# F407ULPI_externalDAC.net
KiCad netlist of a schematic drawn in Altium Designer
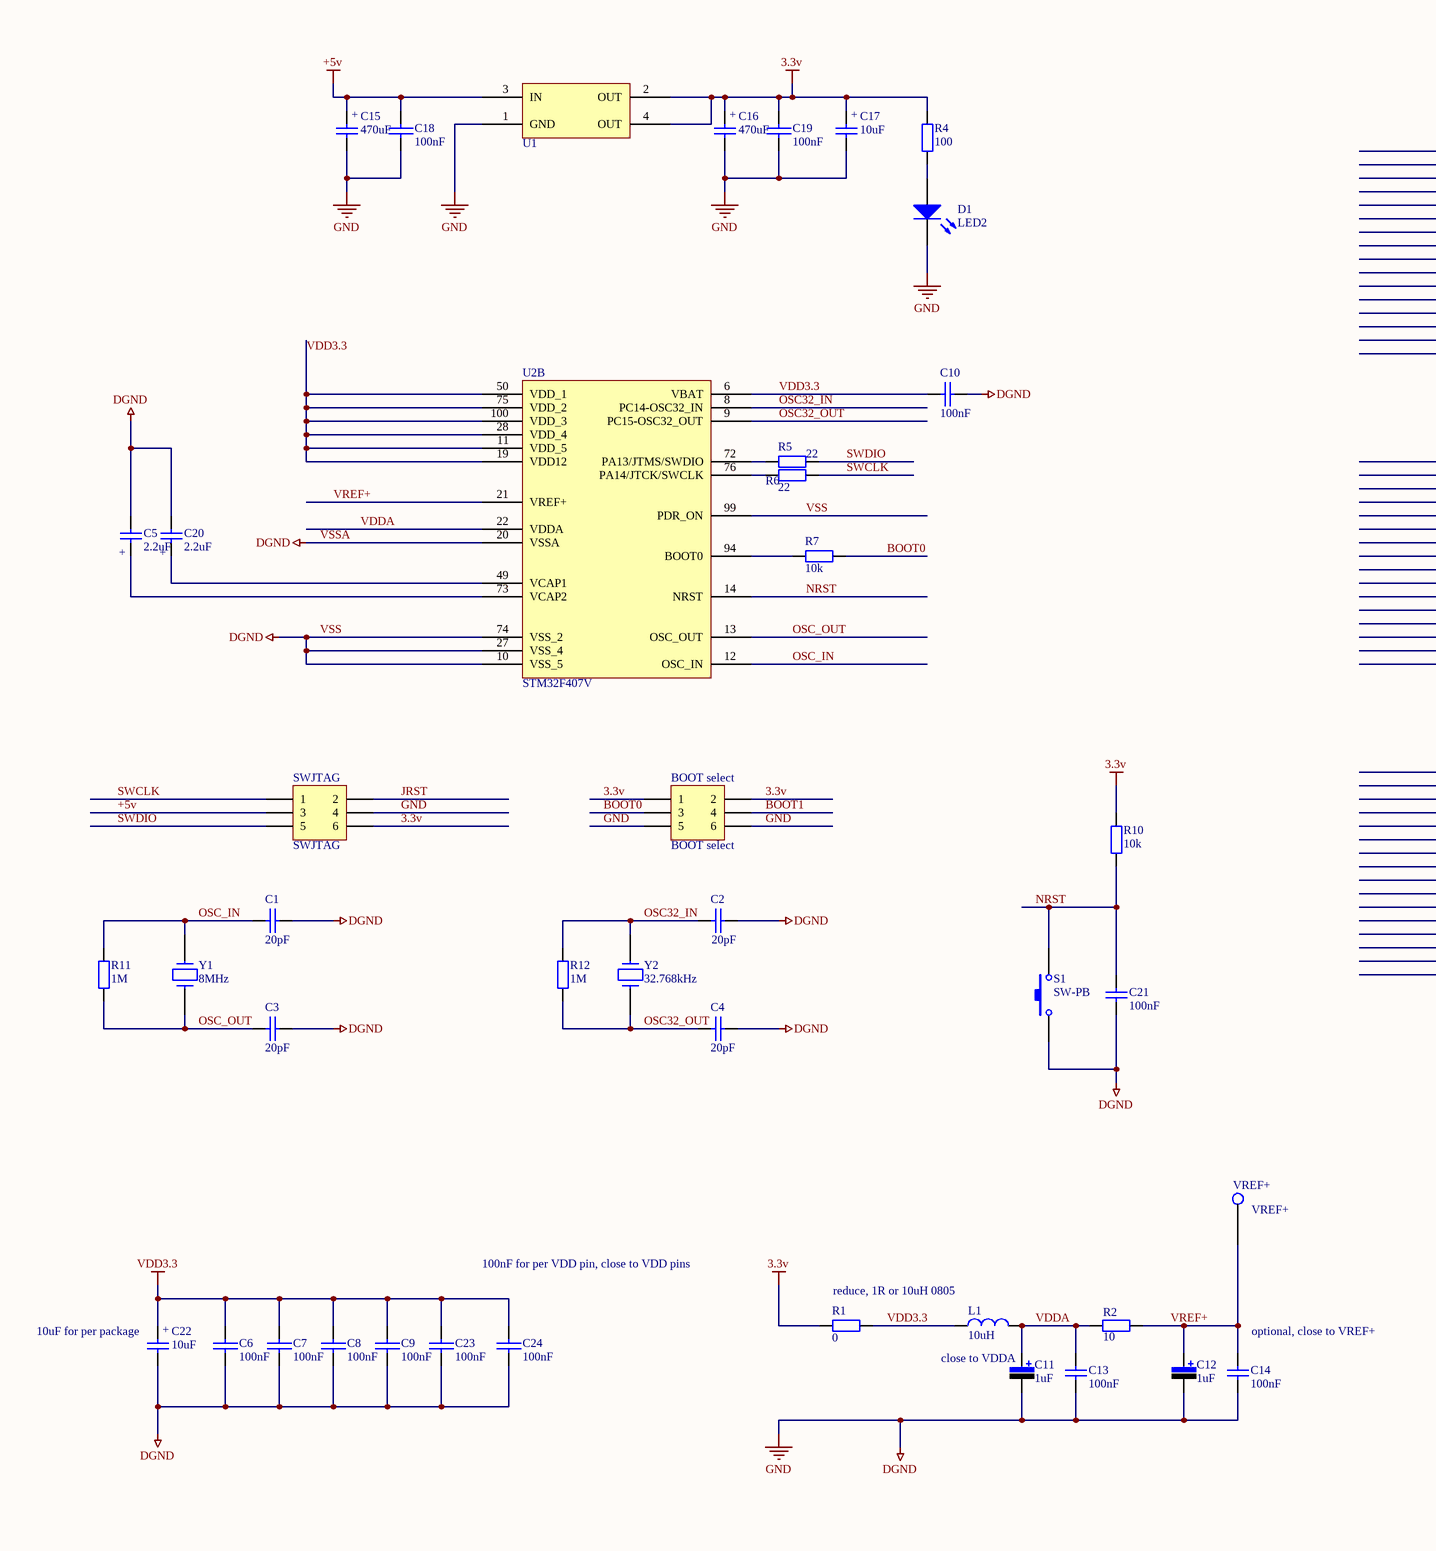
[diagram p0: F407ULPI&externalDAC.SchDoc, left]
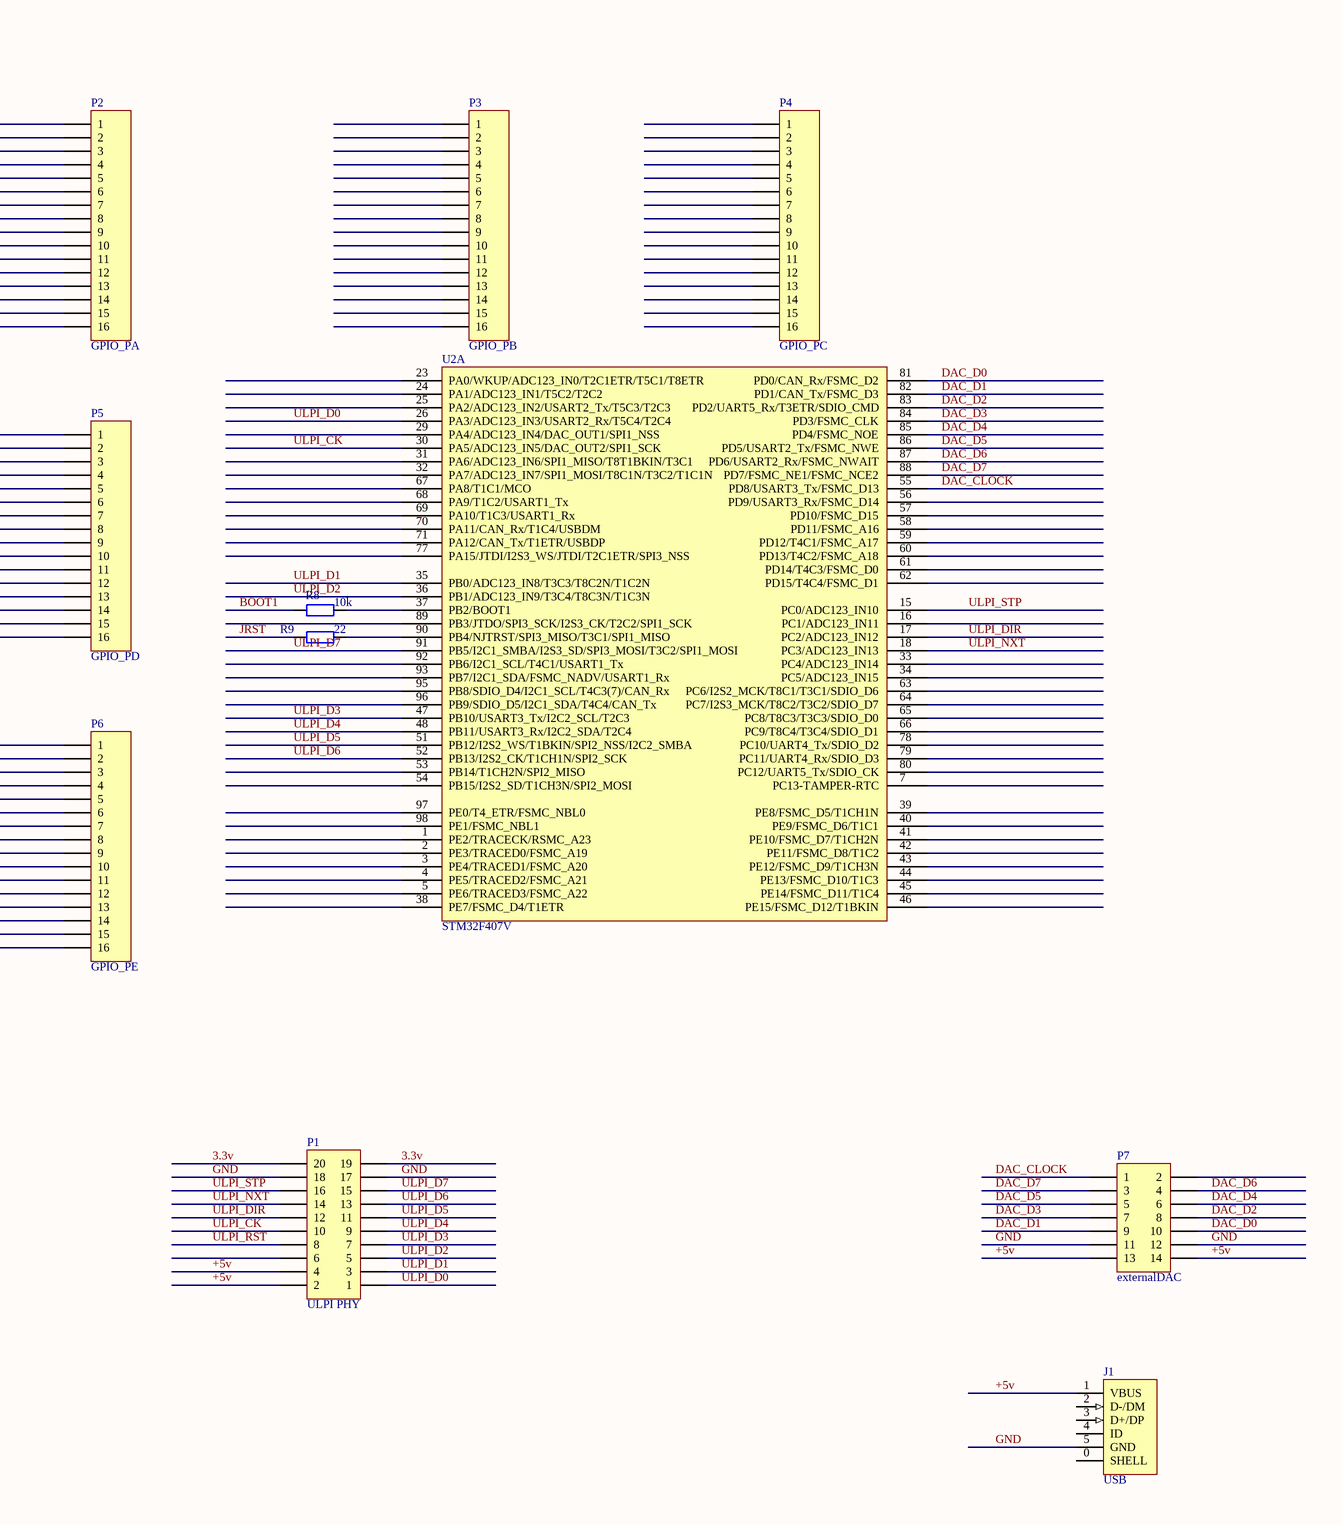
[diagram p1: F407ULPI&externalDAC.SchDoc, right]

(export (version "E")
  (design (tool "Eeschema 10.0.6"))
  (components
    (comp (ref "BOOT select")
      (value "BOOT select")
      (footprint "HDR2X3_CEN")
      (description "Header, 3-Pin, Dual row")
      (fields (field (name "PUBLISHER") "Altium Limited"))
      (libsource (lib "SkyWorks2") (part "Header 3X2"))
    )
    (comp (ref "C1")
      (value "20pF")
      (footprint "CAP-0603")
      (description "贴片无极性电容")
      (fields (field (name "Comment") "cap smd"))
      (libsource (lib "SkyWorks2") (part "CAP"))
    )
    (comp (ref "C2")
      (value "20pF")
      (footprint "CAP-0603")
      (description "贴片无极性电容")
      (fields (field (name "Comment") "cap smd"))
      (libsource (lib "SkyWorks2") (part "CAP"))
    )
    (comp (ref "C3")
      (value "20pF")
      (footprint "CAP-0603")
      (description "贴片无极性电容")
      (fields (field (name "Comment") "cap smd"))
      (libsource (lib "SkyWorks2") (part "CAP"))
    )
    (comp (ref "C4")
      (value "20pF")
      (footprint "CAP-0603")
      (description "贴片无极性电容")
      (fields (field (name "Comment") "cap smd"))
      (libsource (lib "SkyWorks2") (part "CAP"))
    )
    (comp (ref "C5")
      (value "2.2uF")
      (footprint "CAP-3216")
      (description "贴片极性电容")
      (fields (field (name "Comment") "Cap"))
      (libsource (lib "SkyWorks2") (part "Cap Pol S"))
    )
    (comp (ref "C6")
      (value "100nF")
      (footprint "CAP-0603")
      (description "贴片无极性电容")
      (fields (field (name "Comment") "cap smd"))
      (libsource (lib "SkyWorks2") (part "CAP"))
    )
    (comp (ref "C7")
      (value "100nF")
      (footprint "CAP-0603")
      (description "贴片无极性电容")
      (fields (field (name "Comment") "cap smd"))
      (libsource (lib "SkyWorks2") (part "CAP"))
    )
    (comp (ref "C8")
      (value "100nF")
      (footprint "CAP-0603")
      (description "贴片无极性电容")
      (fields (field (name "Comment") "cap smd"))
      (libsource (lib "SkyWorks2") (part "CAP"))
    )
    (comp (ref "C9")
      (value "100nF")
      (footprint "CAP-0603")
      (description "贴片无极性电容")
      (fields (field (name "Comment") "cap smd"))
      (libsource (lib "SkyWorks2") (part "CAP"))
    )
    (comp (ref "C10")
      (value "100nF")
      (footprint "CAP-0603")
      (description "贴片无极性电容")
      (fields (field (name "Comment") "cap smd"))
      (libsource (lib "SkyWorks2") (part "CAP"))
    )
    (comp (ref "C11")
      (value "1uF")
      (footprint "CAP-3216")
      (description "极性电解电容")
      (fields (field (name "Comment") "Cap Pol") (field (name "PUBLISHER") "Altium Limited"))
      (libsource (lib "Fszhang") (part "Cap Pol"))
    )
    (comp (ref "C12")
      (value "1uF")
      (footprint "CAP-3216")
      (description "极性电解电容")
      (fields (field (name "Comment") "Cap Pol") (field (name "PUBLISHER") "Altium Limited"))
      (libsource (lib "Fszhang") (part "Cap Pol"))
    )
    (comp (ref "C13")
      (value "100nF")
      (footprint "CAP-0603")
      (description "无极性电容")
      (fields (field (name "Comment") "Cap") (field (name "PUBLISHER") "Altium Limited"))
      (libsource (lib "Fszhang") (part "Cap"))
    )
    (comp (ref "C14")
      (value "100nF")
      (footprint "CAP-0603")
      (description "无极性电容")
      (fields (field (name "Comment") "Cap") (field (name "PUBLISHER") "Altium Limited"))
      (libsource (lib "Fszhang") (part "Cap"))
    )
    (comp (ref "C15")
      (value "470uF")
      (footprint "CAP-7343")
      (description "贴片极性电容")
      (fields (field (name "Comment") "Cap"))
      (libsource (lib "SkyWorks2") (part "Cap Pol S"))
    )
    (comp (ref "C16")
      (value "470uF")
      (footprint "CAP-7343")
      (description "贴片极性电容")
      (fields (field (name "Comment") "Cap"))
      (libsource (lib "SkyWorks2") (part "Cap Pol S"))
    )
    (comp (ref "C17")
      (value "10uF")
      (footprint "CAP-3216")
      (description "贴片极性电容")
      (fields (field (name "Comment") "Cap"))
      (libsource (lib "SkyWorks2") (part "Cap Pol S"))
    )
    (comp (ref "C18")
      (value "100nF")
      (footprint "CAP-0603")
      (description "贴片无极性电容")
      (fields (field (name "Comment") "cap smd"))
      (libsource (lib "SkyWorks2") (part "CAP"))
    )
    (comp (ref "C19")
      (value "100nF")
      (footprint "CAP-0603")
      (description "贴片无极性电容")
      (fields (field (name "Comment") "cap smd"))
      (libsource (lib "SkyWorks2") (part "CAP"))
    )
    (comp (ref "C20")
      (value "2.2uF")
      (footprint "CAP-3216")
      (description "贴片极性电容")
      (fields (field (name "Comment") "Cap"))
      (libsource (lib "SkyWorks2") (part "Cap Pol S"))
    )
    (comp (ref "C21")
      (value "100nF")
      (footprint "CAP-0603")
      (description "无极性电容")
      (fields (field (name "Comment") "Cap") (field (name "PUBLISHER") "Altium Limited"))
      (libsource (lib "Fszhang") (part "Cap"))
    )
    (comp (ref "C22")
      (value "10uF")
      (footprint "CAP-3216")
      (description "贴片极性电容")
      (fields (field (name "Comment") "Cap"))
      (libsource (lib "SkyWorks2") (part "Cap Pol S"))
    )
    (comp (ref "C23")
      (value "100nF")
      (footprint "CAP-0603")
      (description "贴片无极性电容")
      (fields (field (name "Comment") "cap smd"))
      (libsource (lib "SkyWorks2") (part "CAP"))
    )
    (comp (ref "C24")
      (value "100nF")
      (footprint "CAP-0603")
      (description "贴片无极性电容")
      (fields (field (name "Comment") "cap smd"))
      (libsource (lib "SkyWorks2") (part "CAP"))
    )
    (comp (ref "D1")
      (value "LED2")
      (footprint "LED_0805")
      (description "Typical RED, GREEN, YELLOW, AMBER GaAs LED")
      (fields (field (name "PUBLISHER") "Altium Limited"))
      (libsource (lib "SkyWorks2") (part "LED2"))
    )
    (comp (ref "J1")
      (value "USB")
      (footprint "microUSB")
      (description "USB 2.0, Right Angle, SMT, B Type, Receptacle, 5 Position, Black")
      (fields (field (name "PUBLISHER") "Altium Limited"))
      (libsource (lib "SkyWorks2") (part "Micro_USB"))
    )
    (comp (ref "L1")
      (value "10uH")
      (footprint "0805-1")
      (description "电感")
      (fields (field (name "Comment") "Inductor") (field (name "PUBLISHER") "Altium Limited"))
      (libsource (lib "Fszhang") (part "Inductor"))
    )
    (comp (ref "P1")
      (value "ULPI PHY")
      (footprint "HDR2X10")
      (description "Header, 10-Pin, Dual row")
      (fields (field (name "PUBLISHER") "Altium Limited"))
      (libsource (lib "Miscellaneous Connectors") (part "MHDR2X10"))
    )
    (comp (ref "P2")
      (value "GPIO_PA")
      (footprint "HDR1X16")
      (description "Header, 16-Pin")
      (fields (field (name "PUBLISHER") "Altium Limited"))
      (libsource (lib "Miscellaneous Connectors") (part "Header 16"))
    )
    (comp (ref "P3")
      (value "GPIO_PB")
      (footprint "HDR1X16")
      (description "Header, 16-Pin")
      (fields (field (name "PUBLISHER") "Altium Limited"))
      (libsource (lib "Miscellaneous Connectors") (part "Header 16"))
    )
    (comp (ref "P4")
      (value "GPIO_PC")
      (footprint "HDR1X16")
      (description "Header, 16-Pin")
      (fields (field (name "PUBLISHER") "Altium Limited"))
      (libsource (lib "Miscellaneous Connectors") (part "Header 16"))
    )
    (comp (ref "P5")
      (value "GPIO_PD")
      (footprint "HDR1X16")
      (description "Header, 16-Pin")
      (fields (field (name "PUBLISHER") "Altium Limited"))
      (libsource (lib "Miscellaneous Connectors") (part "Header 16"))
    )
    (comp (ref "P6")
      (value "GPIO_PE")
      (footprint "HDR1X16")
      (description "Header, 16-Pin")
      (fields (field (name "PUBLISHER") "Altium Limited"))
      (libsource (lib "Miscellaneous Connectors") (part "Header 16"))
    )
    (comp (ref "P7")
      (value "externalDAC")
      (footprint "HDR2X7")
      (description "Header, 7-Pin, Dual row")
      (fields (field (name "PUBLISHER") "Altium Limited"))
      (libsource (lib "Miscellaneous Connectors") (part "Header 7X2"))
    )
    (comp (ref "R1")
      (value "0")
      (footprint "CAP-0603")
      (fields (field (name "Comment") "RES1"))
      (libsource (lib "SkyWorks2") (part "RES1"))
    )
    (comp (ref "R2")
      (value "10")
      (footprint "CAP-0603")
      (description "贴片电阻")
      (fields (field (name "Comment") "Res1") (field (name "PUBLISHER") "Altium Limited"))
      (libsource (lib "Fszhang") (part "Res1"))
    )
    (comp (ref "R4")
      (value "100")
      (footprint "CAP-0603")
      (fields (field (name "Comment") "RES1"))
      (libsource (lib "SkyWorks2") (part "RES1"))
    )
    (comp (ref "R5")
      (value "22")
      (footprint "CAP-0603")
      (fields (field (name "Comment") "RES1"))
      (libsource (lib "SkyWorks2") (part "RES1"))
    )
    (comp (ref "R6")
      (value "22")
      (footprint "CAP-0603")
      (fields (field (name "Comment") "RES1"))
      (libsource (lib "SkyWorks2") (part "RES1"))
    )
    (comp (ref "R7")
      (value "10k")
      (footprint "CAP-0603")
      (fields (field (name "Comment") "RES1"))
      (libsource (lib "SkyWorks2") (part "RES1"))
    )
    (comp (ref "R8")
      (value "10k")
      (footprint "CAP-0603")
      (fields (field (name "Comment") "RES1"))
      (libsource (lib "SkyWorks2") (part "RES1"))
    )
    (comp (ref "R9")
      (value "22")
      (footprint "CAP-0603")
      (fields (field (name "Comment") "RES1"))
      (libsource (lib "SkyWorks2") (part "RES1"))
    )
    (comp (ref "R10")
      (value "10k")
      (footprint "R2012[0805]")
      (fields (field (name "Comment") "RES1"))
      (libsource (lib "SkyWorks2") (part "RES1"))
    )
    (comp (ref "R11")
      (value "1M")
      (footprint "R2012[0805]")
      (fields (field (name "Comment") "RES1"))
      (libsource (lib "SkyWorks2") (part "RES1"))
    )
    (comp (ref "R12")
      (value "1M")
      (footprint "R2012[0805]")
      (fields (field (name "Comment") "RES1"))
      (libsource (lib "SkyWorks2") (part "RES1"))
    )
    (comp (ref "S1")
      (value "SW-PB")
      (footprint "SPST-2")
      (description "Switch")
      (fields (field (name "PUBLISHER") "Altium Limited"))
      (libsource (lib "SkyWorks2") (part "SW-PB"))
    )
    (comp (ref "SWJTAG")
      (value "SWJTAG")
      (footprint "HDR2X3_CEN")
      (description "Header, 3-Pin, Dual row")
      (fields (field (name "PUBLISHER") "Altium Limited"))
      (libsource (lib "SkyWorks2") (part "Header 3X2"))
    )
    (comp (ref "U1") (value "1117-3.3") (footprint "SOT223") (libsource (lib "MLI") (part "1117-3.3")))
    (comp (ref "U2")
      (value "STM32F407V")
      (footprint "LQFP-100_M")
      (description "STM32单片机100引脚")
      (libsource (lib "Fszhang") (part "STM32F407V"))
    )
    (comp (ref "VREF+") (value "VREF+") (footprint "HDR1*1") (libsource (lib "MLI") (part "Header 1")))
    (comp (ref "Y1")
      (value "8MHz")
      (footprint "Crystal")
      (description "Crystal")
      (libsource (lib "SkyWorks2") (part "CRYSTAL"))
    )
    (comp (ref "Y2")
      (value "32.768kHz")
      (footprint "Crystal")
      (description "Crystal")
      (libsource (lib "SkyWorks2") (part "CRYSTAL"))
    )
  )
  (nets
    (net (code "1") (name "+5v") (class "Default")
      (node (ref "C15") (pin "1") (pinfunction "+_1") (pintype "passive"))
      (node (ref "C18") (pin "1") (pinfunction "1_1") (pintype "passive"))
      (node (ref "J1") (pin "1") (pinfunction "VBUS_1") (pintype "power_in"))
      (node (ref "P1") (pin "2") (pinfunction "2_2") (pintype "passive"))
      (node (ref "P1") (pin "4") (pinfunction "4_4") (pintype "passive"))
      (node (ref "P7") (pin "13") (pinfunction "13_13") (pintype "passive"))
      (node (ref "P7") (pin "14") (pinfunction "14_14") (pintype "passive"))
      (node (ref "SWJTAG") (pin "3") (pinfunction "3_3") (pintype "passive"))
      (node (ref "U1") (pin "3") (pinfunction "IN_3") (pintype "passive"))
    )
    (net (code "2") (name "/BOOT0") (class "Default")
      (node (ref "BOOT select") (pin "3") (pinfunction "3_3") (pintype "passive"))
      (node (ref "R7") (pin "2") (pinfunction "2_2") (pintype "passive"))
    )
    (net (code "3") (name "/BOOT1") (class "Default")
      (node (ref "BOOT select") (pin "4") (pinfunction "4_4") (pintype "passive"))
      (node (ref "R8") (pin "1") (pinfunction "1_1") (pintype "passive"))
    )
    (net (code "4") (name "/DAC_CLOCK") (class "Default")
      (node (ref "P7") (pin "1") (pinfunction "1_1") (pintype "passive"))
      (node (ref "U2") (pin "55") (pinfunction "PD8/USART3_Tx/FSMC_D13_55") (pintype "passive"))
    )
    (net (code "5") (name "/DAC_D0") (class "Default")
      (node (ref "P7") (pin "10") (pinfunction "10_10") (pintype "passive"))
      (node (ref "U2") (pin "81") (pinfunction "PD0/CAN_Rx/FSMC_D2_81") (pintype "passive"))
    )
    (net (code "6") (name "/DAC_D1") (class "Default")
      (node (ref "P7") (pin "9") (pinfunction "9_9") (pintype "passive"))
      (node (ref "U2") (pin "82") (pinfunction "PD1/CAN_Tx/FSMC_D3_82") (pintype "passive"))
    )
    (net (code "7") (name "/DAC_D2") (class "Default")
      (node (ref "P7") (pin "8") (pinfunction "8_8") (pintype "passive"))
      (node (ref "U2") (pin "83") (pinfunction "PD2/UART5_Rx/T3ETR/SDIO_CMD_83") (pintype "passive"))
    )
    (net (code "8") (name "/DAC_D3") (class "Default")
      (node (ref "P7") (pin "7") (pinfunction "7_7") (pintype "passive"))
      (node (ref "U2") (pin "84") (pinfunction "PD3/FSMC_CLK_84") (pintype "passive"))
    )
    (net (code "9") (name "/DAC_D4") (class "Default")
      (node (ref "P7") (pin "6") (pinfunction "6_6") (pintype "passive"))
      (node (ref "U2") (pin "85") (pinfunction "PD4/FSMC_NOE_85") (pintype "passive"))
    )
    (net (code "10") (name "/DAC_D5") (class "Default")
      (node (ref "P7") (pin "5") (pinfunction "5_5") (pintype "passive"))
      (node (ref "U2") (pin "86") (pinfunction "PD5/USART2_Tx/FSMC_NWE_86") (pintype "passive"))
    )
    (net (code "11") (name "/DAC_D6") (class "Default")
      (node (ref "P7") (pin "4") (pinfunction "4_4") (pintype "passive"))
      (node (ref "U2") (pin "87") (pinfunction "PD6/USART2_Rx/FSMC_NWAIT_87") (pintype "passive"))
    )
    (net (code "12") (name "/DAC_D7") (class "Default")
      (node (ref "P7") (pin "3") (pinfunction "3_3") (pintype "passive"))
      (node (ref "U2") (pin "88") (pinfunction "PD7/FSMC_NE1/FSMC_NCE2_88") (pintype "passive"))
    )
    (net (code "13") (name "/JRST") (class "Default")
      (node (ref "R9") (pin "1") (pinfunction "1_1") (pintype "passive"))
      (node (ref "SWJTAG") (pin "2") (pinfunction "2_2") (pintype "passive"))
    )
    (net (code "14") (name "/NRST") (class "Default")
      (node (ref "C21") (pin "2") (pinfunction "2_2") (pintype "passive"))
      (node (ref "R10") (pin "1") (pinfunction "1_1") (pintype "passive"))
      (node (ref "S1") (pin "2") (pinfunction "2_2") (pintype "passive"))
      (node (ref "U2") (pin "14") (pinfunction "NRST_14") (pintype "passive"))
    )
    (net (code "15") (name "/OSC32_IN") (class "Default")
      (node (ref "C2") (pin "1") (pinfunction "1_1") (pintype "passive"))
      (node (ref "R12") (pin "2") (pinfunction "2_2") (pintype "passive"))
      (node (ref "U2") (pin "8") (pinfunction "PC14-OSC32_IN_8") (pintype "passive"))
      (node (ref "Y2") (pin "2") (pinfunction "2_2") (pintype "passive"))
    )
    (net (code "16") (name "/OSC32_OUT") (class "Default")
      (node (ref "C4") (pin "2") (pinfunction "2_2") (pintype "passive"))
      (node (ref "R12") (pin "1") (pinfunction "1_1") (pintype "passive"))
      (node (ref "U2") (pin "9") (pinfunction "PC15-OSC32_OUT_9") (pintype "passive"))
      (node (ref "Y2") (pin "1") (pinfunction "1_1") (pintype "passive"))
    )
    (net (code "17") (name "/OSC_IN") (class "Default")
      (node (ref "C1") (pin "1") (pinfunction "1_1") (pintype "passive"))
      (node (ref "R11") (pin "2") (pinfunction "2_2") (pintype "passive"))
      (node (ref "U2") (pin "12") (pinfunction "OSC_IN_12") (pintype "passive"))
      (node (ref "Y1") (pin "2") (pinfunction "2_2") (pintype "passive"))
    )
    (net (code "18") (name "/OSC_OUT") (class "Default")
      (node (ref "C3") (pin "2") (pinfunction "2_2") (pintype "passive"))
      (node (ref "R11") (pin "1") (pinfunction "1_1") (pintype "passive"))
      (node (ref "U2") (pin "13") (pinfunction "OSC_OUT_13") (pintype "passive"))
      (node (ref "Y1") (pin "1") (pinfunction "1_1") (pintype "passive"))
    )
    (net (code "19") (name "/SWCLK") (class "Default")
      (node (ref "R6") (pin "2") (pinfunction "2_2") (pintype "passive"))
      (node (ref "SWJTAG") (pin "1") (pinfunction "1_1") (pintype "passive"))
    )
    (net (code "20") (name "/SWDIO") (class "Default")
      (node (ref "R5") (pin "2") (pinfunction "2_2") (pintype "passive"))
      (node (ref "SWJTAG") (pin "5") (pinfunction "5_5") (pintype "passive"))
    )
    (net (code "21") (name "/ULPI_CK") (class "Default")
      (node (ref "P1") (pin "10") (pinfunction "10_10") (pintype "passive"))
      (node (ref "U2") (pin "30") (pinfunction "PA5/ADC123_IN5/DAC_OUT2/SPI1_SCK_30") (pintype "passive"))
    )
    (net (code "22") (name "/ULPI_D0") (class "Default")
      (node (ref "P1") (pin "1") (pinfunction "1_1") (pintype "passive"))
      (node (ref "U2") (pin "26") (pinfunction "PA3/ADC123_IN3/USART2_Rx/T5C4/T2C4_26") (pintype "passive"))
    )
    (net (code "23") (name "/ULPI_D1") (class "Default")
      (node (ref "P1") (pin "3") (pinfunction "3_3") (pintype "passive"))
      (node (ref "U2") (pin "35") (pinfunction "PB0/ADC123_IN8/T3C3/T8C2N/T1C2N_35") (pintype "passive"))
    )
    (net (code "24") (name "/ULPI_D2") (class "Default")
      (node (ref "P1") (pin "5") (pinfunction "5_5") (pintype "passive"))
      (node (ref "U2") (pin "36") (pinfunction "PB1/ADC123_IN9/T3C4/T8C3N/T1C3N_36") (pintype "passive"))
    )
    (net (code "25") (name "/ULPI_D3") (class "Default")
      (node (ref "P1") (pin "7") (pinfunction "7_7") (pintype "passive"))
      (node (ref "U2") (pin "47") (pinfunction "PB10/USART3_Tx/I2C2_SCL/T2C3_47") (pintype "passive"))
    )
    (net (code "26") (name "/ULPI_D4") (class "Default")
      (node (ref "P1") (pin "9") (pinfunction "9_9") (pintype "passive"))
      (node (ref "U2") (pin "48") (pinfunction "PB11/USART3_Rx/I2C2_SDA/T2C4_48") (pintype "passive"))
    )
    (net (code "27") (name "/ULPI_D5") (class "Default")
      (node (ref "P1") (pin "11") (pinfunction "11_11") (pintype "passive"))
      (node (ref "U2") (pin "51") (pinfunction "PB12/I2S2_WS/T1BKIN/SPI2_NSS/I2C2_SMBA_51") (pintype "passive"))
    )
    (net (code "28") (name "/ULPI_D6") (class "Default")
      (node (ref "P1") (pin "13") (pinfunction "13_13") (pintype "passive"))
      (node (ref "U2") (pin "52") (pinfunction "PB13/I2S2_CK/T1CH1N/SPI2_SCK_52") (pintype "passive"))
    )
    (net (code "29") (name "/ULPI_D7") (class "Default")
      (node (ref "P1") (pin "15") (pinfunction "15_15") (pintype "passive"))
      (node (ref "U2") (pin "91") (pinfunction "PB5/I2C1_SMBA/I2S3_SD/SPI3_MOSI/T3C2/SPI1_MOSI_91") (pintype "passive"))
    )
    (net (code "30") (name "/ULPI_DIR") (class "Default")
      (node (ref "P1") (pin "12") (pinfunction "12_12") (pintype "passive"))
      (node (ref "U2") (pin "17") (pinfunction "PC2/ADC123_IN12_17") (pintype "passive"))
    )
    (net (code "31") (name "/ULPI_NXT") (class "Default")
      (node (ref "P1") (pin "14") (pinfunction "14_14") (pintype "passive"))
      (node (ref "U2") (pin "18") (pinfunction "PC3/ADC123_IN13_18") (pintype "passive"))
    )
    (net (code "32") (name "/ULPI_RST") (class "Default")
      (node (ref "P1") (pin "8") (pinfunction "8_8") (pintype "passive"))
    )
    (net (code "33") (name "/ULPI_STP") (class "Default")
      (node (ref "P1") (pin "16") (pinfunction "16_16") (pintype "passive"))
      (node (ref "U2") (pin "15") (pinfunction "PC0/ADC123_IN10_15") (pintype "passive"))
    )
    (net (code "34") (name "/VDDA") (class "Default")
      (node (ref "C11") (pin "1") (pinfunction "1_1") (pintype "passive"))
      (node (ref "C13") (pin "2") (pinfunction "2_2") (pintype "passive"))
      (node (ref "L1") (pin "2") (pinfunction "2_2") (pintype "passive"))
      (node (ref "R2") (pin "1") (pinfunction "1_1") (pintype "passive"))
      (node (ref "U2") (pin "22") (pinfunction "VDDA_22") (pintype "passive"))
    )
    (net (code "35") (name "/VREF+") (class "Default")
      (node (ref "C12") (pin "1") (pinfunction "1_1") (pintype "passive"))
      (node (ref "C14") (pin "2") (pinfunction "2_2") (pintype "passive"))
      (node (ref "R2") (pin "2") (pinfunction "2_2") (pintype "passive"))
      (node (ref "U2") (pin "21") (pinfunction "VREF+_21") (pintype "passive"))
      (node (ref "VREF+") (pin "1") (pinfunction "p_1") (pintype "passive"))
    )
    (net (code "36") (name "3.3v") (class "Default")
      (node (ref "BOOT select") (pin "1") (pinfunction "1_1") (pintype "passive"))
      (node (ref "BOOT select") (pin "2") (pinfunction "2_2") (pintype "passive"))
      (node (ref "C16") (pin "1") (pinfunction "+_1") (pintype "passive"))
      (node (ref "C17") (pin "1") (pinfunction "+_1") (pintype "passive"))
      (node (ref "C19") (pin "1") (pinfunction "1_1") (pintype "passive"))
      (node (ref "P1") (pin "19") (pinfunction "19_19") (pintype "passive"))
      (node (ref "P1") (pin "20") (pinfunction "20_20") (pintype "passive"))
      (node (ref "R1") (pin "1") (pinfunction "1_1") (pintype "passive"))
      (node (ref "R10") (pin "2") (pinfunction "2_2") (pintype "passive"))
      (node (ref "R4") (pin "2") (pinfunction "2_2") (pintype "passive"))
      (node (ref "SWJTAG") (pin "6") (pinfunction "6_6") (pintype "passive"))
      (node (ref "U1") (pin "2") (pinfunction "OUT_2") (pintype "passive"))
      (node (ref "U1") (pin "4") (pinfunction "OUT_4") (pintype "passive"))
    )
    (net (code "37") (name "DGND") (class "Default")
      (node (ref "BOOT select") (pin "5") (pinfunction "5_5") (pintype "passive"))
      (node (ref "BOOT select") (pin "6") (pinfunction "6_6") (pintype "passive"))
      (node (ref "C1") (pin "2") (pinfunction "2_2") (pintype "passive"))
      (node (ref "C10") (pin "1") (pinfunction "1_1") (pintype "passive"))
      (node (ref "C11") (pin "2") (pinfunction "2_2") (pintype "passive"))
      (node (ref "C12") (pin "2") (pinfunction "2_2") (pintype "passive"))
      (node (ref "C13") (pin "1") (pinfunction "1_1") (pintype "passive"))
      (node (ref "C14") (pin "1") (pinfunction "1_1") (pintype "passive"))
      (node (ref "C15") (pin "2") (pinfunction "-_2") (pintype "passive"))
      (node (ref "C16") (pin "2") (pinfunction "-_2") (pintype "passive"))
      (node (ref "C17") (pin "2") (pinfunction "-_2") (pintype "passive"))
      (node (ref "C18") (pin "2") (pinfunction "2_2") (pintype "passive"))
      (node (ref "C19") (pin "2") (pinfunction "2_2") (pintype "passive"))
      (node (ref "C2") (pin "2") (pinfunction "2_2") (pintype "passive"))
      (node (ref "C20") (pin "2") (pinfunction "-_2") (pintype "passive"))
      (node (ref "C21") (pin "1") (pinfunction "1_1") (pintype "passive"))
      (node (ref "C22") (pin "2") (pinfunction "-_2") (pintype "passive"))
      (node (ref "C23") (pin "2") (pinfunction "2_2") (pintype "passive"))
      (node (ref "C24") (pin "2") (pinfunction "2_2") (pintype "passive"))
      (node (ref "C3") (pin "1") (pinfunction "1_1") (pintype "passive"))
      (node (ref "C4") (pin "1") (pinfunction "1_1") (pintype "passive"))
      (node (ref "C5") (pin "2") (pinfunction "-_2") (pintype "passive"))
      (node (ref "C6") (pin "2") (pinfunction "2_2") (pintype "passive"))
      (node (ref "C7") (pin "2") (pinfunction "2_2") (pintype "passive"))
      (node (ref "C8") (pin "2") (pinfunction "2_2") (pintype "passive"))
      (node (ref "C9") (pin "2") (pinfunction "2_2") (pintype "passive"))
      (node (ref "D1") (pin "2") (pinfunction "K_2") (pintype "passive"))
      (node (ref "J1") (pin "5") (pinfunction "GND_5") (pintype "passive"))
      (node (ref "P1") (pin "17") (pinfunction "17_17") (pintype "passive"))
      (node (ref "P1") (pin "18") (pinfunction "18_18") (pintype "passive"))
      (node (ref "P7") (pin "11") (pinfunction "11_11") (pintype "passive"))
      (node (ref "P7") (pin "12") (pinfunction "12_12") (pintype "passive"))
      (node (ref "S1") (pin "1") (pinfunction "1_1") (pintype "passive"))
      (node (ref "SWJTAG") (pin "4") (pinfunction "4_4") (pintype "passive"))
      (node (ref "U1") (pin "1") (pinfunction "GND_1") (pintype "passive"))
      (node (ref "U2") (pin "10") (pinfunction "VSS_5_10") (pintype "passive"))
      (node (ref "U2") (pin "20") (pinfunction "VSSA_20") (pintype "passive"))
      (node (ref "U2") (pin "27") (pinfunction "VSS_4_27") (pintype "passive"))
      (node (ref "U2") (pin "74") (pinfunction "VSS_2_74") (pintype "passive"))
      (node (ref "U2") (pin "99") (pinfunction "PDR_ON_99") (pintype "passive"))
    )
    (net (code "38") (name "Net-(C5-+)") (class "Default")
      (node (ref "C5") (pin "1") (pinfunction "+_1") (pintype "passive"))
      (node (ref "U2") (pin "73") (pinfunction "VCAP2_73") (pintype "passive"))
    )
    (net (code "39") (name "Net-(C20-+)") (class "Default")
      (node (ref "C20") (pin "1") (pinfunction "+_1") (pintype "passive"))
      (node (ref "U2") (pin "49") (pinfunction "VCAP1_49") (pintype "passive"))
    )
    (net (code "40") (name "Net-(D1-A)") (class "Default")
      (node (ref "D1") (pin "1") (pinfunction "A_1") (pintype "passive"))
      (node (ref "R4") (pin "1") (pinfunction "1_1") (pintype "passive"))
    )
    (net (code "41") (name "Net-(U2A-PB2{slash}BOOT1)") (class "Default")
      (node (ref "R8") (pin "2") (pinfunction "2_2") (pintype "passive"))
      (node (ref "U2") (pin "37") (pinfunction "PB2/BOOT1_37") (pintype "passive"))
    )
    (net (code "42") (name "Net-(U2A-PB4{slash}NJTRST{slash}SPI3_MISO{slash}T3C1{slash}SPI1_MISO)") (class "Default")
      (node (ref "R9") (pin "2") (pinfunction "2_2") (pintype "passive"))
      (node (ref "U2") (pin "90") (pinfunction "PB4/NJTRST/SPI3_MISO/T3C1/SPI1_MISO_90") (pintype "passive"))
    )
    (net (code "43") (name "Net-(U2B-BOOT0)") (class "Default")
      (node (ref "R7") (pin "1") (pinfunction "1_1") (pintype "passive"))
      (node (ref "U2") (pin "94") (pinfunction "BOOT0_94") (pintype "passive"))
    )
    (net (code "44") (name "Net-(U2B-PA13{slash}JTMS{slash}SWDIO)") (class "Default")
      (node (ref "R5") (pin "1") (pinfunction "1_1") (pintype "passive"))
      (node (ref "U2") (pin "72") (pinfunction "PA13/JTMS/SWDIO_72") (pintype "passive"))
    )
    (net (code "45") (name "Net-(U2B-PA14{slash}JTCK{slash}SWCLK)") (class "Default")
      (node (ref "R6") (pin "1") (pinfunction "1_1") (pintype "passive"))
      (node (ref "U2") (pin "76") (pinfunction "PA14/JTCK/SWCLK_76") (pintype "passive"))
    )
    (net (code "46") (name "VDD3.3") (class "Default")
      (node (ref "C10") (pin "2") (pinfunction "2_2") (pintype "passive"))
      (node (ref "C22") (pin "1") (pinfunction "+_1") (pintype "passive"))
      (node (ref "C23") (pin "1") (pinfunction "1_1") (pintype "passive"))
      (node (ref "C24") (pin "1") (pinfunction "1_1") (pintype "passive"))
      (node (ref "C6") (pin "1") (pinfunction "1_1") (pintype "passive"))
      (node (ref "C7") (pin "1") (pinfunction "1_1") (pintype "passive"))
      (node (ref "C8") (pin "1") (pinfunction "1_1") (pintype "passive"))
      (node (ref "C9") (pin "1") (pinfunction "1_1") (pintype "passive"))
      (node (ref "L1") (pin "1") (pinfunction "1_1") (pintype "passive"))
      (node (ref "R1") (pin "2") (pinfunction "2_2") (pintype "passive"))
      (node (ref "U2") (pin "100") (pinfunction "VDD_3_100") (pintype "passive"))
      (node (ref "U2") (pin "11") (pinfunction "VDD_5_11") (pintype "passive"))
      (node (ref "U2") (pin "19") (pinfunction "VDD12_19") (pintype "passive"))
      (node (ref "U2") (pin "28") (pinfunction "VDD_4_28") (pintype "passive"))
      (node (ref "U2") (pin "50") (pinfunction "VDD_1_50") (pintype "passive"))
      (node (ref "U2") (pin "6") (pinfunction "VBAT_6") (pintype "passive"))
      (node (ref "U2") (pin "75") (pinfunction "VDD_2_75") (pintype "passive"))
    )
    (net (code "47") (name "unconnected-(J1-D+{slash}DP-Pad3)") (class "Default")
      (node (ref "J1") (pin "3") (pinfunction "D+/DP_3") (pintype "input"))
    )
    (net (code "48") (name "unconnected-(J1-D-{slash}DM-Pad2)") (class "Default")
      (node (ref "J1") (pin "2") (pinfunction "D-/DM_2") (pintype "input"))
    )
    (net (code "49") (name "unconnected-(J1-ID-Pad4)") (class "Default")
      (node (ref "J1") (pin "4") (pinfunction "ID_4") (pintype "power_in"))
    )
    (net (code "50") (name "unconnected-(J1-SHELL-Pad0)") (class "Default")
      (node (ref "J1") (pin "0") (pinfunction "SHELL_0") (pintype "passive"))
    )
    (net (code "51") (name "unconnected-(P1-Pad6)") (class "Default")
      (node (ref "P1") (pin "6") (pinfunction "6_6") (pintype "passive"))
    )
    (net (code "52") (name "unconnected-(P2-Pad1)") (class "Default")
      (node (ref "P2") (pin "1") (pinfunction "1_1") (pintype "passive"))
    )
    (net (code "53") (name "unconnected-(P2-Pad2)") (class "Default")
      (node (ref "P2") (pin "2") (pinfunction "2_2") (pintype "passive"))
    )
    (net (code "54") (name "unconnected-(P2-Pad3)") (class "Default")
      (node (ref "P2") (pin "3") (pinfunction "3_3") (pintype "passive"))
    )
    (net (code "55") (name "unconnected-(P2-Pad4)") (class "Default")
      (node (ref "P2") (pin "4") (pinfunction "4_4") (pintype "passive"))
    )
    (net (code "56") (name "unconnected-(P2-Pad5)") (class "Default")
      (node (ref "P2") (pin "5") (pinfunction "5_5") (pintype "passive"))
    )
    (net (code "57") (name "unconnected-(P2-Pad6)") (class "Default")
      (node (ref "P2") (pin "6") (pinfunction "6_6") (pintype "passive"))
    )
    (net (code "58") (name "unconnected-(P2-Pad7)") (class "Default")
      (node (ref "P2") (pin "7") (pinfunction "7_7") (pintype "passive"))
    )
    (net (code "59") (name "unconnected-(P2-Pad8)") (class "Default")
      (node (ref "P2") (pin "8") (pinfunction "8_8") (pintype "passive"))
    )
    (net (code "60") (name "unconnected-(P2-Pad9)") (class "Default")
      (node (ref "P2") (pin "9") (pinfunction "9_9") (pintype "passive"))
    )
    (net (code "61") (name "unconnected-(P2-Pad10)") (class "Default")
      (node (ref "P2") (pin "10") (pinfunction "10_10") (pintype "passive"))
    )
    (net (code "62") (name "unconnected-(P2-Pad11)") (class "Default")
      (node (ref "P2") (pin "11") (pinfunction "11_11") (pintype "passive"))
    )
    (net (code "63") (name "unconnected-(P2-Pad12)") (class "Default")
      (node (ref "P2") (pin "12") (pinfunction "12_12") (pintype "passive"))
    )
    (net (code "64") (name "unconnected-(P2-Pad13)") (class "Default")
      (node (ref "P2") (pin "13") (pinfunction "13_13") (pintype "passive"))
    )
    (net (code "65") (name "unconnected-(P2-Pad14)") (class "Default")
      (node (ref "P2") (pin "14") (pinfunction "14_14") (pintype "passive"))
    )
    (net (code "66") (name "unconnected-(P2-Pad15)") (class "Default")
      (node (ref "P2") (pin "15") (pinfunction "15_15") (pintype "passive"))
    )
    (net (code "67") (name "unconnected-(P2-Pad16)") (class "Default")
      (node (ref "P2") (pin "16") (pinfunction "16_16") (pintype "passive"))
    )
    (net (code "68") (name "unconnected-(P3-Pad1)") (class "Default")
      (node (ref "P3") (pin "1") (pinfunction "1_1") (pintype "passive"))
    )
    (net (code "69") (name "unconnected-(P3-Pad2)") (class "Default")
      (node (ref "P3") (pin "2") (pinfunction "2_2") (pintype "passive"))
    )
    (net (code "70") (name "unconnected-(P3-Pad3)") (class "Default")
      (node (ref "P3") (pin "3") (pinfunction "3_3") (pintype "passive"))
    )
    (net (code "71") (name "unconnected-(P3-Pad4)") (class "Default")
      (node (ref "P3") (pin "4") (pinfunction "4_4") (pintype "passive"))
    )
    (net (code "72") (name "unconnected-(P3-Pad5)") (class "Default")
      (node (ref "P3") (pin "5") (pinfunction "5_5") (pintype "passive"))
    )
    (net (code "73") (name "unconnected-(P3-Pad6)") (class "Default")
      (node (ref "P3") (pin "6") (pinfunction "6_6") (pintype "passive"))
    )
    (net (code "74") (name "unconnected-(P3-Pad7)") (class "Default")
      (node (ref "P3") (pin "7") (pinfunction "7_7") (pintype "passive"))
    )
    (net (code "75") (name "unconnected-(P3-Pad8)") (class "Default")
      (node (ref "P3") (pin "8") (pinfunction "8_8") (pintype "passive"))
    )
    (net (code "76") (name "unconnected-(P3-Pad9)") (class "Default")
      (node (ref "P3") (pin "9") (pinfunction "9_9") (pintype "passive"))
    )
    (net (code "77") (name "unconnected-(P3-Pad10)") (class "Default")
      (node (ref "P3") (pin "10") (pinfunction "10_10") (pintype "passive"))
    )
    (net (code "78") (name "unconnected-(P3-Pad11)") (class "Default")
      (node (ref "P3") (pin "11") (pinfunction "11_11") (pintype "passive"))
    )
    (net (code "79") (name "unconnected-(P3-Pad12)") (class "Default")
      (node (ref "P3") (pin "12") (pinfunction "12_12") (pintype "passive"))
    )
    (net (code "80") (name "unconnected-(P3-Pad13)") (class "Default")
      (node (ref "P3") (pin "13") (pinfunction "13_13") (pintype "passive"))
    )
    (net (code "81") (name "unconnected-(P3-Pad14)") (class "Default")
      (node (ref "P3") (pin "14") (pinfunction "14_14") (pintype "passive"))
    )
    (net (code "82") (name "unconnected-(P3-Pad15)") (class "Default")
      (node (ref "P3") (pin "15") (pinfunction "15_15") (pintype "passive"))
    )
    (net (code "83") (name "unconnected-(P3-Pad16)") (class "Default")
      (node (ref "P3") (pin "16") (pinfunction "16_16") (pintype "passive"))
    )
    (net (code "84") (name "unconnected-(P4-Pad1)") (class "Default")
      (node (ref "P4") (pin "1") (pinfunction "1_1") (pintype "passive"))
    )
    (net (code "85") (name "unconnected-(P4-Pad2)") (class "Default")
      (node (ref "P4") (pin "2") (pinfunction "2_2") (pintype "passive"))
    )
    (net (code "86") (name "unconnected-(P4-Pad3)") (class "Default")
      (node (ref "P4") (pin "3") (pinfunction "3_3") (pintype "passive"))
    )
    (net (code "87") (name "unconnected-(P4-Pad4)") (class "Default")
      (node (ref "P4") (pin "4") (pinfunction "4_4") (pintype "passive"))
    )
    (net (code "88") (name "unconnected-(P4-Pad5)") (class "Default")
      (node (ref "P4") (pin "5") (pinfunction "5_5") (pintype "passive"))
    )
    (net (code "89") (name "unconnected-(P4-Pad6)") (class "Default")
      (node (ref "P4") (pin "6") (pinfunction "6_6") (pintype "passive"))
    )
    (net (code "90") (name "unconnected-(P4-Pad7)") (class "Default")
      (node (ref "P4") (pin "7") (pinfunction "7_7") (pintype "passive"))
    )
    (net (code "91") (name "unconnected-(P4-Pad8)") (class "Default")
      (node (ref "P4") (pin "8") (pinfunction "8_8") (pintype "passive"))
    )
    (net (code "92") (name "unconnected-(P4-Pad9)") (class "Default")
      (node (ref "P4") (pin "9") (pinfunction "9_9") (pintype "passive"))
    )
    (net (code "93") (name "unconnected-(P4-Pad10)") (class "Default")
      (node (ref "P4") (pin "10") (pinfunction "10_10") (pintype "passive"))
    )
    (net (code "94") (name "unconnected-(P4-Pad11)") (class "Default")
      (node (ref "P4") (pin "11") (pinfunction "11_11") (pintype "passive"))
    )
    (net (code "95") (name "unconnected-(P4-Pad12)") (class "Default")
      (node (ref "P4") (pin "12") (pinfunction "12_12") (pintype "passive"))
    )
    (net (code "96") (name "unconnected-(P4-Pad13)") (class "Default")
      (node (ref "P4") (pin "13") (pinfunction "13_13") (pintype "passive"))
    )
    (net (code "97") (name "unconnected-(P4-Pad14)") (class "Default")
      (node (ref "P4") (pin "14") (pinfunction "14_14") (pintype "passive"))
    )
    (net (code "98") (name "unconnected-(P4-Pad15)") (class "Default")
      (node (ref "P4") (pin "15") (pinfunction "15_15") (pintype "passive"))
    )
    (net (code "99") (name "unconnected-(P4-Pad16)") (class "Default")
      (node (ref "P4") (pin "16") (pinfunction "16_16") (pintype "passive"))
    )
    (net (code "100") (name "unconnected-(P5-Pad1)") (class "Default")
      (node (ref "P5") (pin "1") (pinfunction "1_1") (pintype "passive"))
    )
    (net (code "101") (name "unconnected-(P5-Pad2)") (class "Default")
      (node (ref "P5") (pin "2") (pinfunction "2_2") (pintype "passive"))
    )
    (net (code "102") (name "unconnected-(P5-Pad3)") (class "Default")
      (node (ref "P5") (pin "3") (pinfunction "3_3") (pintype "passive"))
    )
    (net (code "103") (name "unconnected-(P5-Pad4)") (class "Default")
      (node (ref "P5") (pin "4") (pinfunction "4_4") (pintype "passive"))
    )
    (net (code "104") (name "unconnected-(P5-Pad5)") (class "Default")
      (node (ref "P5") (pin "5") (pinfunction "5_5") (pintype "passive"))
    )
    (net (code "105") (name "unconnected-(P5-Pad6)") (class "Default")
      (node (ref "P5") (pin "6") (pinfunction "6_6") (pintype "passive"))
    )
    (net (code "106") (name "unconnected-(P5-Pad7)") (class "Default")
      (node (ref "P5") (pin "7") (pinfunction "7_7") (pintype "passive"))
    )
    (net (code "107") (name "unconnected-(P5-Pad8)") (class "Default")
      (node (ref "P5") (pin "8") (pinfunction "8_8") (pintype "passive"))
    )
    (net (code "108") (name "unconnected-(P5-Pad9)") (class "Default")
      (node (ref "P5") (pin "9") (pinfunction "9_9") (pintype "passive"))
    )
    (net (code "109") (name "unconnected-(P5-Pad10)") (class "Default")
      (node (ref "P5") (pin "10") (pinfunction "10_10") (pintype "passive"))
    )
    (net (code "110") (name "unconnected-(P5-Pad11)") (class "Default")
      (node (ref "P5") (pin "11") (pinfunction "11_11") (pintype "passive"))
    )
    (net (code "111") (name "unconnected-(P5-Pad12)") (class "Default")
      (node (ref "P5") (pin "12") (pinfunction "12_12") (pintype "passive"))
    )
    (net (code "112") (name "unconnected-(P5-Pad13)") (class "Default")
      (node (ref "P5") (pin "13") (pinfunction "13_13") (pintype "passive"))
    )
    (net (code "113") (name "unconnected-(P5-Pad14)") (class "Default")
      (node (ref "P5") (pin "14") (pinfunction "14_14") (pintype "passive"))
    )
    (net (code "114") (name "unconnected-(P5-Pad15)") (class "Default")
      (node (ref "P5") (pin "15") (pinfunction "15_15") (pintype "passive"))
    )
    (net (code "115") (name "unconnected-(P5-Pad16)") (class "Default")
      (node (ref "P5") (pin "16") (pinfunction "16_16") (pintype "passive"))
    )
    (net (code "116") (name "unconnected-(P6-Pad1)") (class "Default")
      (node (ref "P6") (pin "1") (pinfunction "1_1") (pintype "passive"))
    )
    (net (code "117") (name "unconnected-(P6-Pad2)") (class "Default")
      (node (ref "P6") (pin "2") (pinfunction "2_2") (pintype "passive"))
    )
    (net (code "118") (name "unconnected-(P6-Pad3)") (class "Default")
      (node (ref "P6") (pin "3") (pinfunction "3_3") (pintype "passive"))
    )
    (net (code "119") (name "unconnected-(P6-Pad4)") (class "Default")
      (node (ref "P6") (pin "4") (pinfunction "4_4") (pintype "passive"))
    )
    (net (code "120") (name "unconnected-(P6-Pad5)") (class "Default")
      (node (ref "P6") (pin "5") (pinfunction "5_5") (pintype "passive"))
    )
    (net (code "121") (name "unconnected-(P6-Pad6)") (class "Default")
      (node (ref "P6") (pin "6") (pinfunction "6_6") (pintype "passive"))
    )
    (net (code "122") (name "unconnected-(P6-Pad7)") (class "Default")
      (node (ref "P6") (pin "7") (pinfunction "7_7") (pintype "passive"))
    )
    (net (code "123") (name "unconnected-(P6-Pad8)") (class "Default")
      (node (ref "P6") (pin "8") (pinfunction "8_8") (pintype "passive"))
    )
    (net (code "124") (name "unconnected-(P6-Pad9)") (class "Default")
      (node (ref "P6") (pin "9") (pinfunction "9_9") (pintype "passive"))
    )
    (net (code "125") (name "unconnected-(P6-Pad10)") (class "Default")
      (node (ref "P6") (pin "10") (pinfunction "10_10") (pintype "passive"))
    )
    (net (code "126") (name "unconnected-(P6-Pad11)") (class "Default")
      (node (ref "P6") (pin "11") (pinfunction "11_11") (pintype "passive"))
    )
    (net (code "127") (name "unconnected-(P6-Pad12)") (class "Default")
      (node (ref "P6") (pin "12") (pinfunction "12_12") (pintype "passive"))
    )
    (net (code "128") (name "unconnected-(P6-Pad13)") (class "Default")
      (node (ref "P6") (pin "13") (pinfunction "13_13") (pintype "passive"))
    )
    (net (code "129") (name "unconnected-(P6-Pad14)") (class "Default")
      (node (ref "P6") (pin "14") (pinfunction "14_14") (pintype "passive"))
    )
    (net (code "130") (name "unconnected-(P6-Pad15)") (class "Default")
      (node (ref "P6") (pin "15") (pinfunction "15_15") (pintype "passive"))
    )
    (net (code "131") (name "unconnected-(P6-Pad16)") (class "Default")
      (node (ref "P6") (pin "16") (pinfunction "16_16") (pintype "passive"))
    )
    (net (code "132") (name "unconnected-(P7-Pad2)") (class "Default")
      (node (ref "P7") (pin "2") (pinfunction "2_2") (pintype "passive"))
    )
    (net (code "133") (name "unconnected-(U2A-PA0{slash}WKUP{slash}ADC123_IN0{slash}T2C1ETR{slash}T5C1{slash}T8ETR-Pad23)") (class "Default")
      (node (ref "U2") (pin "23") (pinfunction "PA0/WKUP/ADC123_IN0/T2C1ETR/T5C1/T8ETR_23") (pintype "passive"))
    )
    (net (code "134") (name "unconnected-(U2A-PA1{slash}ADC123_IN1{slash}T5C2{slash}T2C2-Pad24)") (class "Default")
      (node (ref "U2") (pin "24") (pinfunction "PA1/ADC123_IN1/T5C2/T2C2_24") (pintype "passive"))
    )
    (net (code "135") (name "unconnected-(U2A-PA2{slash}ADC123_IN2{slash}USART2_Tx{slash}T5C3{slash}T2C3-Pad25)") (class "Default")
      (node (ref "U2") (pin "25") (pinfunction "PA2/ADC123_IN2/USART2_Tx/T5C3/T2C3_25") (pintype "passive"))
    )
    (net (code "136") (name "unconnected-(U2A-PA4{slash}ADC123_IN4{slash}DAC_OUT1{slash}SPI1_NSS-Pad29)") (class "Default")
      (node (ref "U2") (pin "29") (pinfunction "PA4/ADC123_IN4/DAC_OUT1/SPI1_NSS_29") (pintype "passive"))
    )
    (net (code "137") (name "unconnected-(U2A-PA6{slash}ADC123_IN6{slash}SPI1_MISO{slash}T8T1BKIN{slash}T3C1-Pad31)") (class "Default")
      (node (ref "U2") (pin "31") (pinfunction "PA6/ADC123_IN6/SPI1_MISO/T8T1BKIN/T3C1_31") (pintype "passive"))
    )
    (net (code "138") (name "unconnected-(U2A-PA7{slash}ADC123_IN7{slash}SPI1_MOSI{slash}T8C1N{slash}T3C2{slash}T1C1N-Pad32)") (class "Default")
      (node (ref "U2") (pin "32") (pinfunction "PA7/ADC123_IN7/SPI1_MOSI/T8C1N/T3C2/T1C1N_32") (pintype "passive"))
    )
    (net (code "139") (name "unconnected-(U2A-PA8{slash}T1C1{slash}MCO-Pad67)") (class "Default")
      (node (ref "U2") (pin "67") (pinfunction "PA8/T1C1/MCO_67") (pintype "passive"))
    )
    (net (code "140") (name "unconnected-(U2A-PA9{slash}T1C2{slash}USART1_Tx-Pad68)") (class "Default")
      (node (ref "U2") (pin "68") (pinfunction "PA9/T1C2/USART1_Tx_68") (pintype "passive"))
    )
    (net (code "141") (name "unconnected-(U2A-PA10{slash}T1C3{slash}USART1_Rx-Pad69)") (class "Default")
      (node (ref "U2") (pin "69") (pinfunction "PA10/T1C3/USART1_Rx_69") (pintype "passive"))
    )
    (net (code "142") (name "unconnected-(U2A-PA11{slash}CAN_Rx{slash}T1C4{slash}USBDM-Pad70)") (class "Default")
      (node (ref "U2") (pin "70") (pinfunction "PA11/CAN_Rx/T1C4/USBDM_70") (pintype "passive"))
    )
    (net (code "143") (name "unconnected-(U2A-PA12{slash}CAN_Tx{slash}T1ETR{slash}USBDP-Pad71)") (class "Default")
      (node (ref "U2") (pin "71") (pinfunction "PA12/CAN_Tx/T1ETR/USBDP_71") (pintype "passive"))
    )
    (net (code "144") (name "unconnected-(U2A-PA15{slash}JTDI{slash}I2S3_WS{slash}JTDI{slash}T2C1ETR{slash}SPI3_NSS-Pad77)") (class "Default")
      (node (ref "U2") (pin "77") (pinfunction "PA15/JTDI/I2S3_WS/JTDI/T2C1ETR/SPI3_NSS_77") (pintype "passive"))
    )
    (net (code "145") (name "unconnected-(U2A-PB3{slash}JTDO{slash}SPI3_SCK{slash}I2S3_CK{slash}T2C2{slash}SPI1_SCK-Pad89)") (class "Default")
      (node (ref "U2") (pin "89") (pinfunction "PB3/JTDO/SPI3_SCK/I2S3_CK/T2C2/SPI1_SCK_89") (pintype "passive"))
    )
    (net (code "146") (name "unconnected-(U2A-PB6{slash}I2C1_SCL{slash}T4C1{slash}USART1_Tx-Pad92)") (class "Default")
      (node (ref "U2") (pin "92") (pinfunction "PB6/I2C1_SCL/T4C1/USART1_Tx_92") (pintype "passive"))
    )
    (net (code "147") (name "unconnected-(U2A-PB7{slash}I2C1_SDA{slash}FSMC_NADV{slash}USART1_Rx-Pad93)") (class "Default")
      (node (ref "U2") (pin "93") (pinfunction "PB7/I2C1_SDA/FSMC_NADV/USART1_Rx_93") (pintype "passive"))
    )
    (net (code "148") (name "unconnected-(U2A-PB8{slash}SDIO_D4{slash}I2C1_SCL{slash}T4C3(7){slash}CAN_Rx-Pad95)") (class "Default")
      (node (ref "U2") (pin "95") (pinfunction "PB8/SDIO_D4/I2C1_SCL/T4C3(7)/CAN_Rx_95") (pintype "passive"))
    )
    (net (code "149") (name "unconnected-(U2A-PB9{slash}SDIO_D5{slash}I2C1_SDA{slash}T4C4{slash}CAN_Tx-Pad96)") (class "Default")
      (node (ref "U2") (pin "96") (pinfunction "PB9/SDIO_D5/I2C1_SDA/T4C4/CAN_Tx_96") (pintype "passive"))
    )
    (net (code "150") (name "unconnected-(U2A-PB14{slash}T1CH2N{slash}SPI2_MISO-Pad53)") (class "Default")
      (node (ref "U2") (pin "53") (pinfunction "PB14/T1CH2N/SPI2_MISO_53") (pintype "passive"))
    )
    (net (code "151") (name "unconnected-(U2A-PB15{slash}I2S2_SD{slash}T1CH3N{slash}SPI2_MOSI-Pad54)") (class "Default")
      (node (ref "U2") (pin "54") (pinfunction "PB15/I2S2_SD/T1CH3N/SPI2_MOSI_54") (pintype "passive"))
    )
    (net (code "152") (name "unconnected-(U2A-PC1{slash}ADC123_IN11-Pad16)") (class "Default")
      (node (ref "U2") (pin "16") (pinfunction "PC1/ADC123_IN11_16") (pintype "passive"))
    )
    (net (code "153") (name "unconnected-(U2A-PC4{slash}ADC123_IN14-Pad33)") (class "Default")
      (node (ref "U2") (pin "33") (pinfunction "PC4/ADC123_IN14_33") (pintype "passive"))
    )
    (net (code "154") (name "unconnected-(U2A-PC5{slash}ADC123_IN15-Pad34)") (class "Default")
      (node (ref "U2") (pin "34") (pinfunction "PC5/ADC123_IN15_34") (pintype "passive"))
    )
    (net (code "155") (name "unconnected-(U2A-PC6{slash}I2S2_MCK{slash}T8C1{slash}T3C1{slash}SDIO_D6-Pad63)") (class "Default")
      (node (ref "U2") (pin "63") (pinfunction "PC6/I2S2_MCK/T8C1/T3C1/SDIO_D6_63") (pintype "passive"))
    )
    (net (code "156") (name "unconnected-(U2A-PC7{slash}I2S3_MCK{slash}T8C2{slash}T3C2{slash}SDIO_D7-Pad64)") (class "Default")
      (node (ref "U2") (pin "64") (pinfunction "PC7/I2S3_MCK/T8C2/T3C2/SDIO_D7_64") (pintype "passive"))
    )
    (net (code "157") (name "unconnected-(U2A-PC8{slash}T8C3{slash}T3C3{slash}SDIO_D0-Pad65)") (class "Default")
      (node (ref "U2") (pin "65") (pinfunction "PC8/T8C3/T3C3/SDIO_D0_65") (pintype "passive"))
    )
    (net (code "158") (name "unconnected-(U2A-PC9{slash}T8C4{slash}T3C4{slash}SDIO_D1-Pad66)") (class "Default")
      (node (ref "U2") (pin "66") (pinfunction "PC9/T8C4/T3C4/SDIO_D1_66") (pintype "passive"))
    )
    (net (code "159") (name "unconnected-(U2A-PC10{slash}UART4_Tx{slash}SDIO_D2-Pad78)") (class "Default")
      (node (ref "U2") (pin "78") (pinfunction "PC10/UART4_Tx/SDIO_D2_78") (pintype "passive"))
    )
    (net (code "160") (name "unconnected-(U2A-PC11{slash}UART4_Rx{slash}SDIO_D3-Pad79)") (class "Default")
      (node (ref "U2") (pin "79") (pinfunction "PC11/UART4_Rx/SDIO_D3_79") (pintype "passive"))
    )
    (net (code "161") (name "unconnected-(U2A-PC12{slash}UART5_Tx{slash}SDIO_CK-Pad80)") (class "Default")
      (node (ref "U2") (pin "80") (pinfunction "PC12/UART5_Tx/SDIO_CK_80") (pintype "passive"))
    )
    (net (code "162") (name "unconnected-(U2A-PC13-TAMPER-RTC-Pad7)") (class "Default")
      (node (ref "U2") (pin "7") (pinfunction "PC13-TAMPER-RTC_7") (pintype "passive"))
    )
    (net (code "163") (name "unconnected-(U2A-PD9{slash}USART3_Rx{slash}FSMC_D14-Pad56)") (class "Default")
      (node (ref "U2") (pin "56") (pinfunction "PD9/USART3_Rx/FSMC_D14_56") (pintype "passive"))
    )
    (net (code "164") (name "unconnected-(U2A-PD10{slash}FSMC_D15-Pad57)") (class "Default")
      (node (ref "U2") (pin "57") (pinfunction "PD10/FSMC_D15_57") (pintype "passive"))
    )
    (net (code "165") (name "unconnected-(U2A-PD11{slash}FSMC_A16-Pad58)") (class "Default")
      (node (ref "U2") (pin "58") (pinfunction "PD11/FSMC_A16_58") (pintype "passive"))
    )
    (net (code "166") (name "unconnected-(U2A-PD12{slash}T4C1{slash}FSMC_A17-Pad59)") (class "Default")
      (node (ref "U2") (pin "59") (pinfunction "PD12/T4C1/FSMC_A17_59") (pintype "passive"))
    )
    (net (code "167") (name "unconnected-(U2A-PD13{slash}T4C2{slash}FSMC_A18-Pad60)") (class "Default")
      (node (ref "U2") (pin "60") (pinfunction "PD13/T4C2/FSMC_A18_60") (pintype "passive"))
    )
    (net (code "168") (name "unconnected-(U2A-PD14{slash}T4C3{slash}FSMC_D0-Pad61)") (class "Default")
      (node (ref "U2") (pin "61") (pinfunction "PD14/T4C3/FSMC_D0_61") (pintype "passive"))
    )
    (net (code "169") (name "unconnected-(U2A-PD15{slash}T4C4{slash}FSMC_D1-Pad62)") (class "Default")
      (node (ref "U2") (pin "62") (pinfunction "PD15/T4C4/FSMC_D1_62") (pintype "passive"))
    )
    (net (code "170") (name "unconnected-(U2A-PE0{slash}T4_ETR{slash}FSMC_NBL0-Pad97)") (class "Default")
      (node (ref "U2") (pin "97") (pinfunction "PE0/T4_ETR/FSMC_NBL0_97") (pintype "passive"))
    )
    (net (code "171") (name "unconnected-(U2A-PE1{slash}FSMC_NBL1-Pad98)") (class "Default")
      (node (ref "U2") (pin "98") (pinfunction "PE1/FSMC_NBL1_98") (pintype "passive"))
    )
    (net (code "172") (name "unconnected-(U2A-PE2{slash}TRACECK{slash}RSMC_A23-Pad1)") (class "Default")
      (node (ref "U2") (pin "1") (pinfunction "PE2/TRACECK/RSMC_A23_1") (pintype "passive"))
    )
    (net (code "173") (name "unconnected-(U2A-PE3{slash}TRACED0{slash}FSMC_A19-Pad2)") (class "Default")
      (node (ref "U2") (pin "2") (pinfunction "PE3/TRACED0/FSMC_A19_2") (pintype "passive"))
    )
    (net (code "174") (name "unconnected-(U2A-PE4{slash}TRACED1{slash}FSMC_A20-Pad3)") (class "Default")
      (node (ref "U2") (pin "3") (pinfunction "PE4/TRACED1/FSMC_A20_3") (pintype "passive"))
    )
    (net (code "175") (name "unconnected-(U2A-PE5{slash}TRACED2{slash}FSMC_A21-Pad4)") (class "Default")
      (node (ref "U2") (pin "4") (pinfunction "PE5/TRACED2/FSMC_A21_4") (pintype "passive"))
    )
    (net (code "176") (name "unconnected-(U2A-PE6{slash}TRACED3{slash}FSMC_A22-Pad5)") (class "Default")
      (node (ref "U2") (pin "5") (pinfunction "PE6/TRACED3/FSMC_A22_5") (pintype "passive"))
    )
    (net (code "177") (name "unconnected-(U2A-PE7{slash}FSMC_D4{slash}T1ETR-Pad38)") (class "Default")
      (node (ref "U2") (pin "38") (pinfunction "PE7/FSMC_D4/T1ETR_38") (pintype "passive"))
    )
    (net (code "178") (name "unconnected-(U2A-PE8{slash}FSMC_D5{slash}T1CH1N-Pad39)") (class "Default")
      (node (ref "U2") (pin "39") (pinfunction "PE8/FSMC_D5/T1CH1N_39") (pintype "passive"))
    )
    (net (code "179") (name "unconnected-(U2A-PE9{slash}FSMC_D6{slash}T1C1-Pad40)") (class "Default")
      (node (ref "U2") (pin "40") (pinfunction "PE9/FSMC_D6/T1C1_40") (pintype "passive"))
    )
    (net (code "180") (name "unconnected-(U2A-PE10{slash}FSMC_D7{slash}T1CH2N-Pad41)") (class "Default")
      (node (ref "U2") (pin "41") (pinfunction "PE10/FSMC_D7/T1CH2N_41") (pintype "passive"))
    )
    (net (code "181") (name "unconnected-(U2A-PE11{slash}FSMC_D8{slash}T1C2-Pad42)") (class "Default")
      (node (ref "U2") (pin "42") (pinfunction "PE11/FSMC_D8/T1C2_42") (pintype "passive"))
    )
    (net (code "182") (name "unconnected-(U2A-PE12{slash}FSMC_D9{slash}T1CH3N-Pad43)") (class "Default")
      (node (ref "U2") (pin "43") (pinfunction "PE12/FSMC_D9/T1CH3N_43") (pintype "passive"))
    )
    (net (code "183") (name "unconnected-(U2A-PE13{slash}FSMC_D10{slash}T1C3-Pad44)") (class "Default")
      (node (ref "U2") (pin "44") (pinfunction "PE13/FSMC_D10/T1C3_44") (pintype "passive"))
    )
    (net (code "184") (name "unconnected-(U2A-PE14{slash}FSMC_D11{slash}T1C4-Pad45)") (class "Default")
      (node (ref "U2") (pin "45") (pinfunction "PE14/FSMC_D11/T1C4_45") (pintype "passive"))
    )
    (net (code "185") (name "unconnected-(U2A-PE15{slash}FSMC_D12{slash}T1BKIN-Pad46)") (class "Default")
      (node (ref "U2") (pin "46") (pinfunction "PE15/FSMC_D12/T1BKIN_46") (pintype "passive"))
    )
  )
)
